# 2_5V.net
KiCad netlist of a schematic drawn in Altium Designer
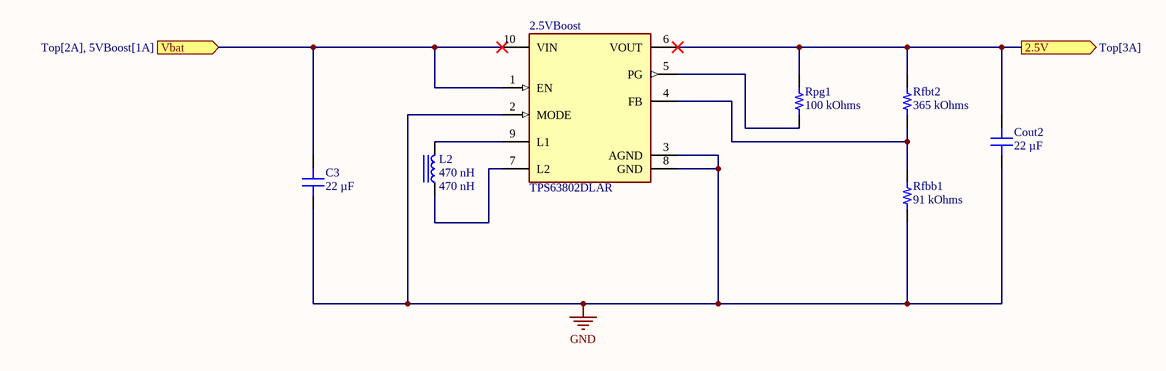
[diagram p0: 2.5V.SchDoc]

(export (version "E")
  (design (tool "Eeschema 10.0.6"))
  (components
    (comp (ref "2.5VBoost")
      (value "TPS63802DLAR")
      (footprint "FP-DLA0010A-MFG")
      (description "IC POWER MANAGEMENT")
      (fields
        (field (name "OCTOPART") "https://octopart.com/tps63802dlar-texas+instruments-97359678")
        (field (name "MANUFACTURER") "Texas Instruments")
      )
      (libsource (lib "Altium Content Vault") (part "f9a6115c6bf72e8ba457236a565d59e"))
    )
    (comp (ref "C3")
      (value "22 µF")
      (footprint "CAP 0603_1608")
      (description "CAP CER 22UF 10V X5R 0603")
      (fields (field (name "TOLERANCE") "±20%") (field (name "PART NUMBER") "CL10A226MPCNUBE"))
      (libsource (lib "Gopher Motorsports") (part "CAPACITOR"))
    )
    (comp (ref "Cout2")
      (value "22 µF")
      (footprint "CAP 0603_1608")
      (description "CAP CER 22UF 10V X5R 0603")
      (fields (field (name "TOLERANCE") "±20%") (field (name "PART NUMBER") "CL10A226MPCNUBE"))
      (libsource (lib "Gopher Motorsports") (part "CAPACITOR"))
    )
    (comp (ref "L2")
      (value "470 nH")
      (footprint "BOURNS SRP5030T")
      (description "FIXED IND 470NH 12A 7.4 MOHM SMD")
      (fields
        (field (name "MANUFACTURER") "Bourns Inc.")
        (field (name "INDUCTANCE") "470 nH")
        (field (name "TOLERANCE") "±20%")
      )
      (libsource (lib "Gopher Motorsports") (part "INDUCTOR"))
    )
    (comp (ref "Rfbb1")
      (value "91 kOhms")
      (footprint "RES 0603_1608")
      (description "RES SMD 91K OHM 1% 1/4W 0603")
      (fields
        (field (name "MANUFACTURER") "Panasonic Electronic Components")
        (field (name "TOLERANCE") "±1%")
      )
      (libsource (lib "Gopher Motorsports") (part "RESISTOR"))
    )
    (comp (ref "Rfbt2")
      (value "365 kOhms")
      (footprint "RES 0603_1608")
      (description "RES 365K OHM 1% 1/10W 0603")
      (fields (field (name "TOLERANCE") "±1%") (field (name "MANUFACTURER") "Yageo"))
      (libsource (lib "Gopher Motorsports") (part "RESISTOR"))
    )
    (comp (ref "Rpg1")
      (value "100 kOhms")
      (footprint "RES 0603_1608")
      (description "RES 100K OHM 5% 1/10W 0603")
      (fields (field (name "TOLERANCE") "±5%") (field (name "PART NUMBER") "RK73B1JTTD104J"))
      (libsource (lib "Gopher Motorsports") (part "RESISTOR"))
    )
  )
  (nets
    (net (code "1") (name "/2.5V") (class "Default")
      (node (ref "2.5VBoost") (pin "6") (pinfunction "VOUT_6") (pintype "power_in"))
      (node (ref "Cout2") (pin "2") (pinfunction "2_2") (pintype "passive"))
      (node (ref "Rfbt2") (pin "2") (pinfunction "2_2") (pintype "passive"))
      (node (ref "Rpg1") (pin "2") (pinfunction "2_2") (pintype "passive"))
    )
    (net (code "2") (name "/Vbat") (class "Default")
      (node (ref "2.5VBoost") (pin "1") (pinfunction "EN_1") (pintype "input"))
      (node (ref "2.5VBoost") (pin "10") (pinfunction "VIN_10") (pintype "power_in"))
      (node (ref "C3") (pin "2") (pinfunction "2_2") (pintype "passive"))
    )
    (net (code "3") (name "GND") (class "Default")
      (node (ref "2.5VBoost") (pin "2") (pinfunction "MODE_2") (pintype "input"))
      (node (ref "2.5VBoost") (pin "3") (pinfunction "AGND_3") (pintype "power_in"))
      (node (ref "2.5VBoost") (pin "8") (pinfunction "GND_8") (pintype "power_in"))
      (node (ref "C3") (pin "1") (pinfunction "1_1") (pintype "passive"))
      (node (ref "Cout2") (pin "1") (pinfunction "1_1") (pintype "passive"))
      (node (ref "Rfbb1") (pin "1") (pinfunction "1_1") (pintype "passive"))
    )
    (net (code "4") (name "Net-(2.5VBoost-FB)") (class "Default")
      (node (ref "2.5VBoost") (pin "4") (pinfunction "FB_4") (pintype "passive"))
      (node (ref "Rfbb1") (pin "2") (pinfunction "2_2") (pintype "passive"))
      (node (ref "Rfbt2") (pin "1") (pinfunction "1_1") (pintype "passive"))
    )
    (net (code "5") (name "Net-(2.5VBoost-L1)") (class "Default")
      (node (ref "2.5VBoost") (pin "9") (pinfunction "L1_9") (pintype "passive"))
      (node (ref "L2") (pin "2") (pinfunction "2_2") (pintype "passive"))
    )
    (net (code "6") (name "Net-(2.5VBoost-L2)") (class "Default")
      (node (ref "2.5VBoost") (pin "7") (pinfunction "L2_7") (pintype "passive"))
      (node (ref "L2") (pin "1") (pinfunction "1_1") (pintype "passive"))
    )
    (net (code "7") (name "Net-(2.5VBoost-PG)") (class "Default")
      (node (ref "2.5VBoost") (pin "5") (pinfunction "PG_5") (pintype "output"))
      (node (ref "Rpg1") (pin "1") (pinfunction "1_1") (pintype "passive"))
    )
  )
)
